# fpga2.net
KiCad netlist of a schematic drawn in Altium Designer
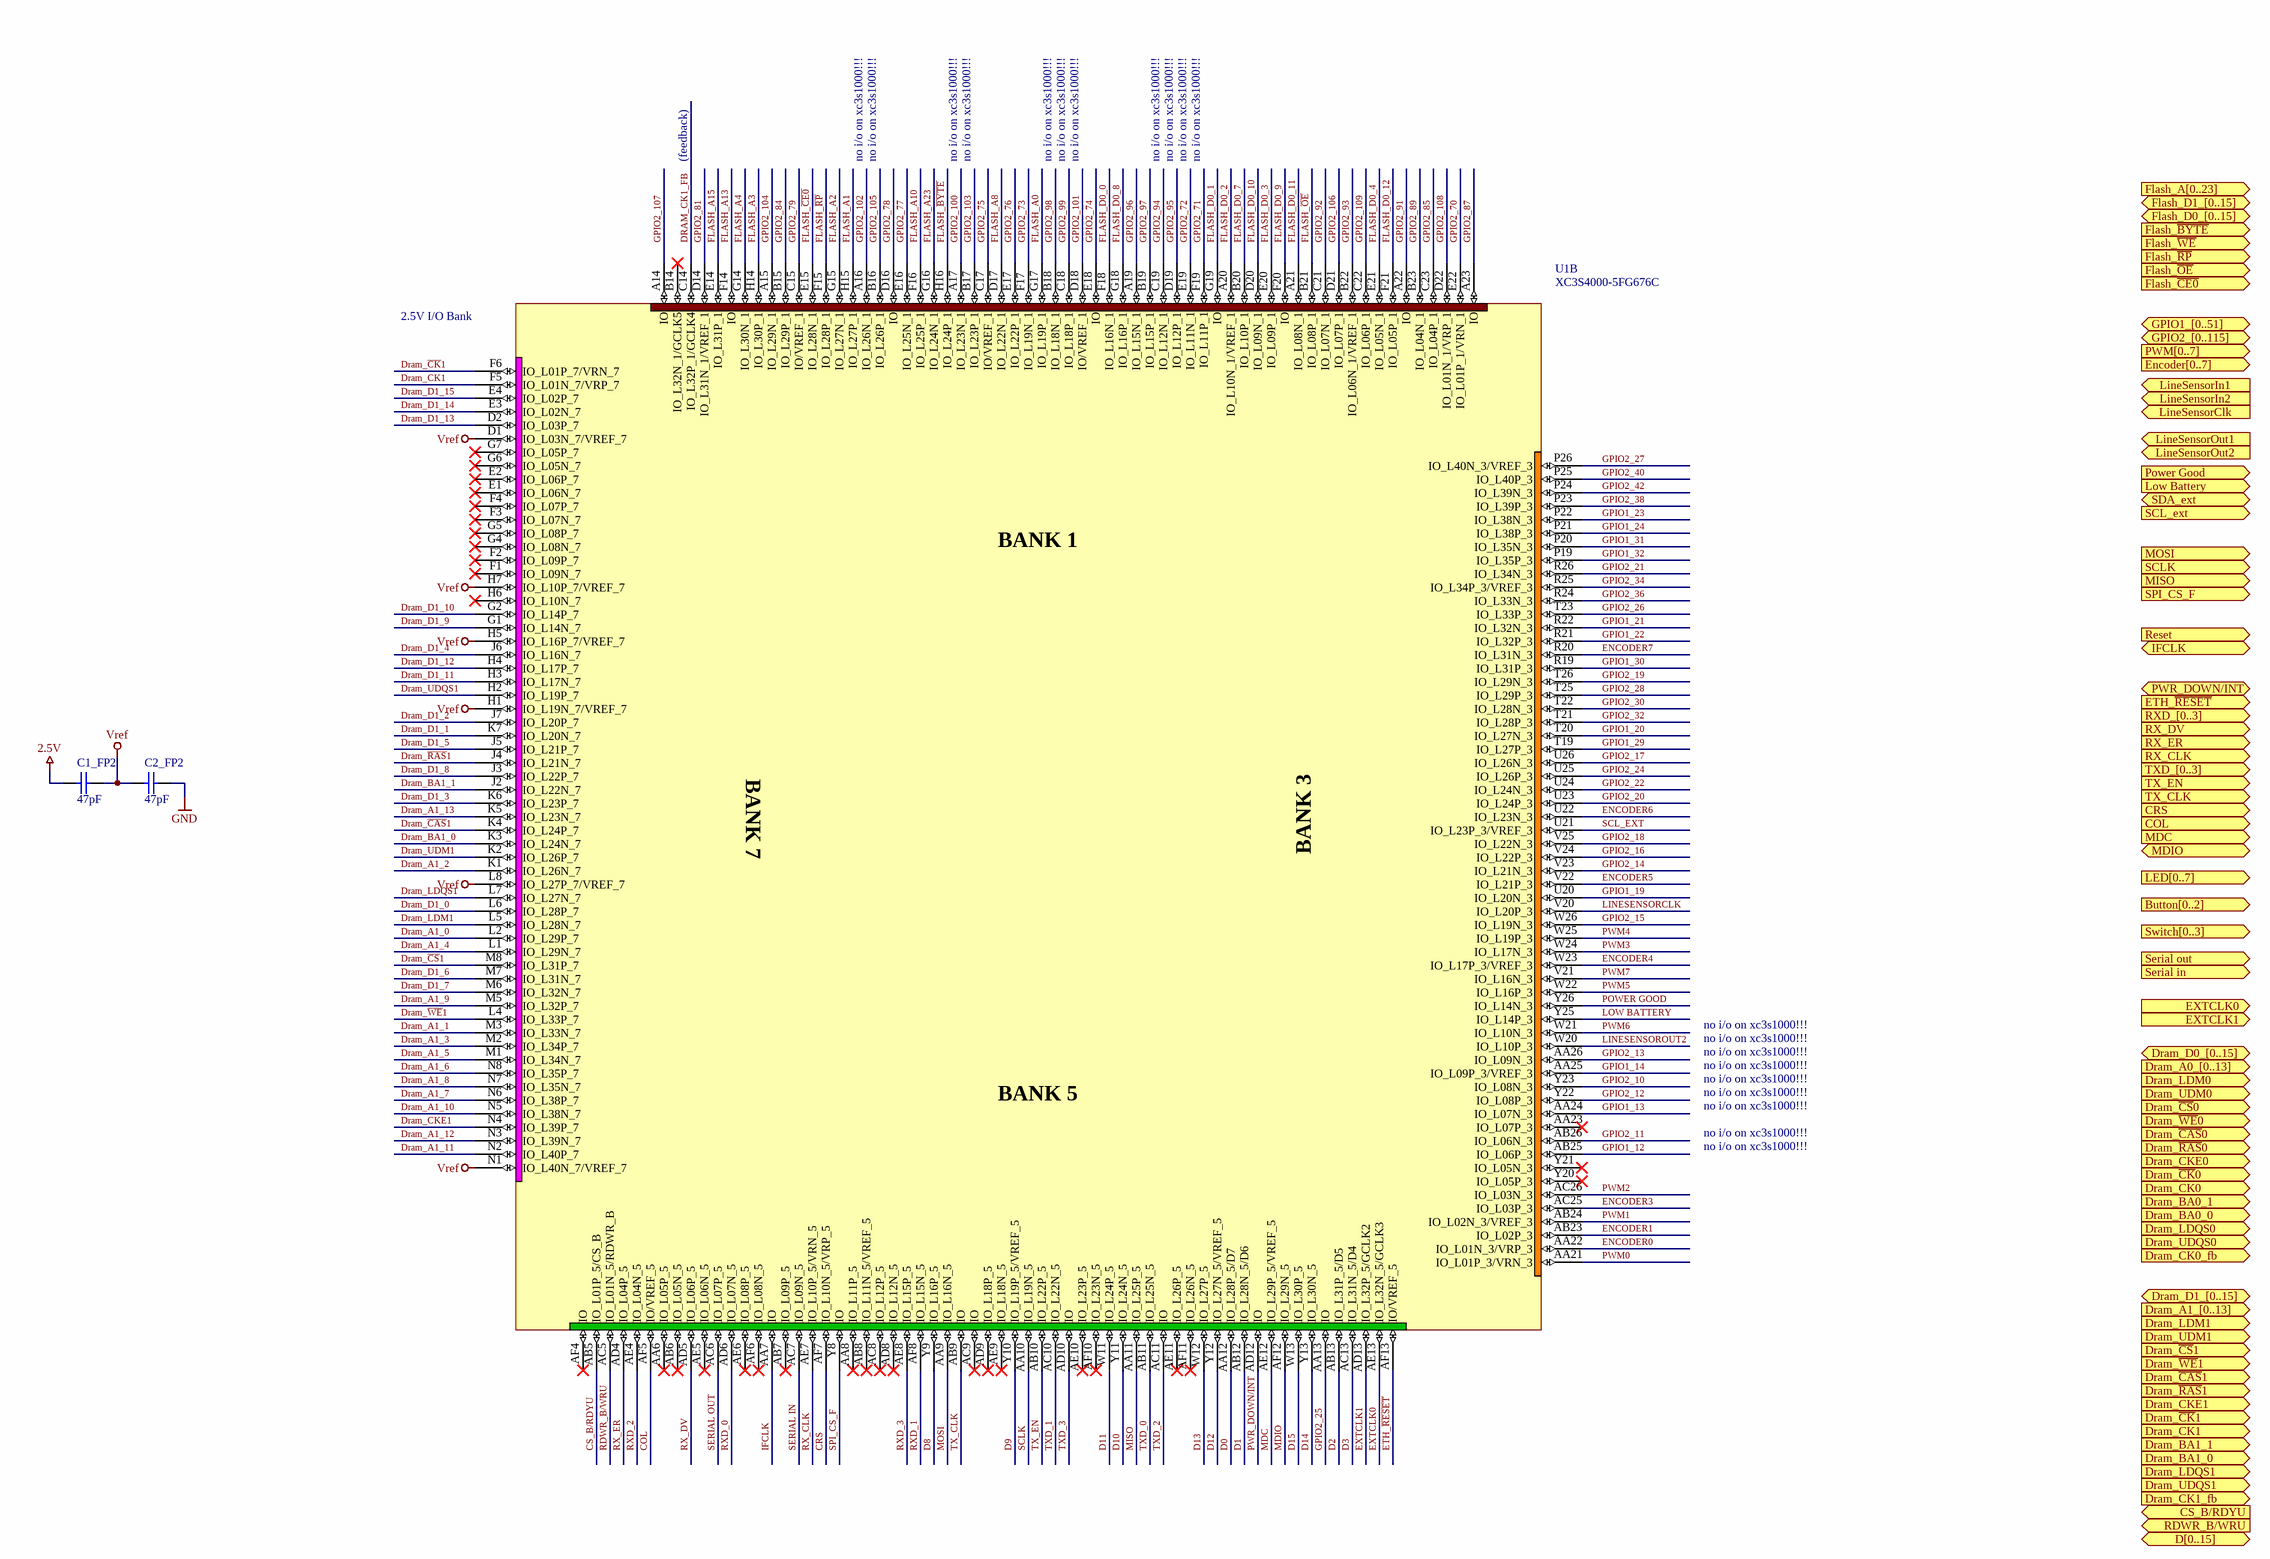
[diagram p0: fpga2.SCHDOC]

(export (version "E")
  (design (tool "Eeschema 10.0.6"))
  (components
    (comp (ref "C1_FP2")
      (value "47pF")
      (footprint "0402")
      (description "Capacitor")
      (fields
        (field (name "MANUFACTURER") "Murata")
        (field (name "PART NUMBER") "GRM1555C1H470JZ01D")
        (field (name "PUBLISHER") "Altium Limited")
      )
      (libsource (lib "Miscellaneous Devices") (part "Cap"))
    )
    (comp (ref "C2_FP2")
      (value "47pF")
      (footprint "0402")
      (description "Capacitor")
      (fields
        (field (name "MANUFACTURER") "Murata")
        (field (name "PART NUMBER") "GRM1555C1H470JZ01D")
        (field (name "PUBLISHER") "Altium Limited")
      )
      (libsource (lib "Miscellaneous Devices") (part "Cap"))
    )
    (comp (ref "U1")
      (value "XC3S4000-5FG676C")
      (footprint "FG676")
      (description "Spartan-3 1.2V FPGA, 487 User I/Os, 676-ball FBGA, High Performance, Commercial Grade")
      (fields (field (name "MANUFACTURER") "Xilinx") (field (name "PUBLISHER") "Altium Limited"))
      (libsource (lib "gecko3-user") (part "XC3S1500-5FG676C"))
    )
  )
  (nets
    (net (code "211") (name "/COL") (class "Default")
      (node (ref "U1") (pin "AF5") (pinfunction "IO/VREF_5_AF5") (pintype "bidirectional"))
    )
    (net (code "212") (name "/CRS") (class "Default")
      (node (ref "U1") (pin "AF7") (pinfunction "IO_L10N_5/VRP_5_AF7") (pintype "bidirectional"))
    )
    (net (code "213") (name "/CS_B{slash}RDYU") (class "Default")
      (node (ref "U1") (pin "AB5") (pinfunction "IO_L01P_5/CS_B_AB5") (pintype "bidirectional"))
    )
    (net (code "214") (name "/D0") (class "Default")
      (node (ref "U1") (pin "AA12") (pinfunction "IO_L28P_5/D7_AA12") (pintype "bidirectional"))
    )
    (net (code "215") (name "/D1") (class "Default")
      (node (ref "U1") (pin "AB12") (pinfunction "IO_L28N_5/D6_AB12") (pintype "bidirectional"))
    )
    (net (code "216") (name "/D2") (class "Default")
      (node (ref "U1") (pin "AB13") (pinfunction "IO_L31P_5/D5_AB13") (pintype "bidirectional"))
    )
    (net (code "217") (name "/D3") (class "Default")
      (node (ref "U1") (pin "AC13") (pinfunction "IO_L31N_5/D4_AC13") (pintype "bidirectional"))
    )
    (net (code "218") (name "/D8") (class "Default")
      (node (ref "U1") (pin "Y9") (pinfunction "IO_L16P_5_Y9") (pintype "bidirectional"))
    )
    (net (code "219") (name "/D9") (class "Default")
      (node (ref "U1") (pin "Y10") (pinfunction "IO_L19P_5/VREF_5_Y10") (pintype "bidirectional"))
    )
    (net (code "220") (name "/D10") (class "Default")
      (node (ref "U1") (pin "Y11") (pinfunction "IO_L24N_5_Y11") (pintype "bidirectional"))
    )
    (net (code "221") (name "/D11") (class "Default")
      (node (ref "U1") (pin "W11") (pinfunction "IO_L24P_5_W11") (pintype "bidirectional"))
    )
    (net (code "222") (name "/D12") (class "Default")
      (node (ref "U1") (pin "Y12") (pinfunction "IO_L27N_5/VREF_5_Y12") (pintype "bidirectional"))
    )
    (net (code "223") (name "/D13") (class "Default")
      (node (ref "U1") (pin "W12") (pinfunction "IO_L27P_5_W12") (pintype "bidirectional"))
    )
    (net (code "224") (name "/D14") (class "Default")
      (node (ref "U1") (pin "Y13") (pinfunction "IO_L30N_5_Y13") (pintype "bidirectional"))
    )
    (net (code "225") (name "/D15") (class "Default")
      (node (ref "U1") (pin "W13") (pinfunction "IO_L30P_5_W13") (pintype "bidirectional"))
    )
    (net (code "226") (name "/DRAM_CK1_FB") (class "Default")
      (node (ref "U1") (pin "C14") (pinfunction "IO_L32P_1/GCLK4_C14") (pintype "bidirectional"))
    )
    (net (code "229") (name "/Dram_A1_0") (class "Default")
      (node (ref "U1") (pin "L2") (pinfunction "IO_L29P_7_L2") (pintype "bidirectional"))
    )
    (net (code "230") (name "/Dram_A1_1") (class "Default")
      (node (ref "U1") (pin "M3") (pinfunction "IO_L33N_7_M3") (pintype "bidirectional"))
    )
    (net (code "231") (name "/Dram_A1_2") (class "Default")
      (node (ref "U1") (pin "K1") (pinfunction "IO_L26N_7_K1") (pintype "bidirectional"))
    )
    (net (code "232") (name "/Dram_A1_3") (class "Default")
      (node (ref "U1") (pin "M2") (pinfunction "IO_L34P_7_M2") (pintype "bidirectional"))
    )
    (net (code "233") (name "/Dram_A1_4") (class "Default")
      (node (ref "U1") (pin "L1") (pinfunction "IO_L29N_7_L1") (pintype "bidirectional"))
    )
    (net (code "234") (name "/Dram_A1_5") (class "Default")
      (node (ref "U1") (pin "M1") (pinfunction "IO_L34N_7_M1") (pintype "bidirectional"))
    )
    (net (code "235") (name "/Dram_A1_6") (class "Default")
      (node (ref "U1") (pin "N8") (pinfunction "IO_L35P_7_N8") (pintype "bidirectional"))
    )
    (net (code "236") (name "/Dram_A1_7") (class "Default")
      (node (ref "U1") (pin "N6") (pinfunction "IO_L38P_7_N6") (pintype "bidirectional"))
    )
    (net (code "237") (name "/Dram_A1_8") (class "Default")
      (node (ref "U1") (pin "N7") (pinfunction "IO_L35N_7_N7") (pintype "bidirectional"))
    )
    (net (code "238") (name "/Dram_A1_9") (class "Default")
      (node (ref "U1") (pin "M5") (pinfunction "IO_L32P_7_M5") (pintype "bidirectional"))
    )
    (net (code "239") (name "/Dram_A1_10") (class "Default")
      (node (ref "U1") (pin "N5") (pinfunction "IO_L38N_7_N5") (pintype "bidirectional"))
    )
    (net (code "240") (name "/Dram_A1_11") (class "Default")
      (node (ref "U1") (pin "N2") (pinfunction "IO_L40P_7_N2") (pintype "bidirectional"))
    )
    (net (code "241") (name "/Dram_A1_12") (class "Default")
      (node (ref "U1") (pin "N3") (pinfunction "IO_L39N_7_N3") (pintype "bidirectional"))
    )
    (net (code "242") (name "/Dram_A1_13") (class "Default")
      (node (ref "U1") (pin "K5") (pinfunction "IO_L23N_7_K5") (pintype "bidirectional"))
    )
    (net (code "246") (name "/Dram_BA1_0") (class "Default")
      (node (ref "U1") (pin "K3") (pinfunction "IO_L24N_7_K3") (pintype "bidirectional"))
    )
    (net (code "247") (name "/Dram_BA1_1") (class "Default")
      (node (ref "U1") (pin "J2") (pinfunction "IO_L22N_7_J2") (pintype "bidirectional"))
    )
    (net (code "250") (name "/Dram_CK1") (class "Default")
      (node (ref "U1") (pin "F5") (pinfunction "IO_L01N_7/VRP_7_F5") (pintype "bidirectional"))
    )
    (net (code "253") (name "/Dram_CKE1") (class "Default")
      (node (ref "U1") (pin "N4") (pinfunction "IO_L39P_7_N4") (pintype "bidirectional"))
    )
    (net (code "255") (name "/Dram_D1_0") (class "Default")
      (node (ref "U1") (pin "L6") (pinfunction "IO_L28P_7_L6") (pintype "bidirectional"))
    )
    (net (code "256") (name "/Dram_D1_1") (class "Default")
      (node (ref "U1") (pin "K7") (pinfunction "IO_L20N_7_K7") (pintype "bidirectional"))
    )
    (net (code "257") (name "/Dram_D1_2") (class "Default")
      (node (ref "U1") (pin "J7") (pinfunction "IO_L20P_7_J7") (pintype "bidirectional"))
    )
    (net (code "258") (name "/Dram_D1_3") (class "Default")
      (node (ref "U1") (pin "K6") (pinfunction "IO_L23P_7_K6") (pintype "bidirectional"))
    )
    (net (code "259") (name "/Dram_D1_4") (class "Default")
      (node (ref "U1") (pin "J6") (pinfunction "IO_L16N_7_J6") (pintype "bidirectional"))
    )
    (net (code "260") (name "/Dram_D1_5") (class "Default")
      (node (ref "U1") (pin "J5") (pinfunction "IO_L21P_7_J5") (pintype "bidirectional"))
    )
    (net (code "261") (name "/Dram_D1_6") (class "Default")
      (node (ref "U1") (pin "M7") (pinfunction "IO_L31N_7_M7") (pintype "bidirectional"))
    )
    (net (code "262") (name "/Dram_D1_7") (class "Default")
      (node (ref "U1") (pin "M6") (pinfunction "IO_L32N_7_M6") (pintype "bidirectional"))
    )
    (net (code "263") (name "/Dram_D1_8") (class "Default")
      (node (ref "U1") (pin "J3") (pinfunction "IO_L22P_7_J3") (pintype "bidirectional"))
    )
    (net (code "264") (name "/Dram_D1_9") (class "Default")
      (node (ref "U1") (pin "G1") (pinfunction "IO_L14N_7_G1") (pintype "bidirectional"))
    )
    (net (code "265") (name "/Dram_D1_10") (class "Default")
      (node (ref "U1") (pin "G2") (pinfunction "IO_L14P_7_G2") (pintype "bidirectional"))
    )
    (net (code "266") (name "/Dram_D1_11") (class "Default")
      (node (ref "U1") (pin "H3") (pinfunction "IO_L17N_7_H3") (pintype "bidirectional"))
    )
    (net (code "267") (name "/Dram_D1_12") (class "Default")
      (node (ref "U1") (pin "H4") (pinfunction "IO_L17P_7_H4") (pintype "bidirectional"))
    )
    (net (code "268") (name "/Dram_D1_13") (class "Default")
      (node (ref "U1") (pin "D2") (pinfunction "IO_L03P_7_D2") (pintype "bidirectional"))
    )
    (net (code "269") (name "/Dram_D1_14") (class "Default")
      (node (ref "U1") (pin "E3") (pinfunction "IO_L02N_7_E3") (pintype "bidirectional"))
    )
    (net (code "270") (name "/Dram_D1_15") (class "Default")
      (node (ref "U1") (pin "E4") (pinfunction "IO_L02P_7_E4") (pintype "bidirectional"))
    )
    (net (code "273") (name "/Dram_LDM1") (class "Default")
      (node (ref "U1") (pin "L5") (pinfunction "IO_L28N_7_L5") (pintype "bidirectional"))
    )
    (net (code "275") (name "/Dram_LDQS1") (class "Default")
      (node (ref "U1") (pin "L7") (pinfunction "IO_L27N_7_L7") (pintype "bidirectional"))
    )
    (net (code "277") (name "/Dram_UDM1") (class "Default")
      (node (ref "U1") (pin "K2") (pinfunction "IO_L26P_7_K2") (pintype "bidirectional"))
    )
    (net (code "279") (name "/Dram_UDQS1") (class "Default")
      (node (ref "U1") (pin "H2") (pinfunction "IO_L19P_7_H2") (pintype "bidirectional"))
    )
    (net (code "281") (name "/Dram_~{CAS}1") (class "Default")
      (node (ref "U1") (pin "K4") (pinfunction "IO_L24P_7_K4") (pintype "bidirectional"))
    )
    (net (code "283") (name "/Dram_~{CK}1") (class "Default")
      (node (ref "U1") (pin "F6") (pinfunction "IO_L01P_7/VRN_7_F6") (pintype "bidirectional"))
    )
    (net (code "285") (name "/Dram_~{CS}1") (class "Default")
      (node (ref "U1") (pin "M8") (pinfunction "IO_L31P_7_M8") (pintype "bidirectional"))
    )
    (net (code "287") (name "/Dram_~{RAS}1") (class "Default")
      (node (ref "U1") (pin "J4") (pinfunction "IO_L21N_7_J4") (pintype "bidirectional"))
    )
    (net (code "289") (name "/Dram_~{WE}1") (class "Default")
      (node (ref "U1") (pin "L4") (pinfunction "IO_L33P_7_L4") (pintype "bidirectional"))
    )
    (net (code "290") (name "/ENCODER0") (class "Default")
      (node (ref "U1") (pin "AA22") (pinfunction "IO_L01N_3/VRP_3_AA22") (pintype "bidirectional"))
    )
    (net (code "291") (name "/ENCODER1") (class "Default")
      (node (ref "U1") (pin "AB23") (pinfunction "IO_L02P_3_AB23") (pintype "bidirectional"))
    )
    (net (code "292") (name "/ENCODER3") (class "Default")
      (node (ref "U1") (pin "AC25") (pinfunction "IO_L03P_3_AC25") (pintype "bidirectional"))
    )
    (net (code "293") (name "/ENCODER4") (class "Default")
      (node (ref "U1") (pin "W23") (pinfunction "IO_L17P_3/VREF_3_W23") (pintype "bidirectional"))
    )
    (net (code "294") (name "/ENCODER5") (class "Default")
      (node (ref "U1") (pin "V22") (pinfunction "IO_L21P_3_V22") (pintype "bidirectional"))
    )
    (net (code "295") (name "/ENCODER6") (class "Default")
      (node (ref "U1") (pin "U22") (pinfunction "IO_L23N_3_U22") (pintype "bidirectional"))
    )
    (net (code "296") (name "/ENCODER7") (class "Default")
      (node (ref "U1") (pin "R20") (pinfunction "IO_L31N_3_R20") (pintype "bidirectional"))
    )
    (net (code "297") (name "/ETH_~{RESET}") (class "Default")
      (node (ref "U1") (pin "AF13") (pinfunction "IO/VREF_5_AF13") (pintype "bidirectional"))
    )
    (net (code "298") (name "/EXTCLK0") (class "Default")
      (node (ref "U1") (pin "AE13") (pinfunction "IO_L32N_5/GCLK3_AE13") (pintype "bidirectional"))
    )
    (net (code "299") (name "/EXTCLK1") (class "Default")
      (node (ref "U1") (pin "AD13") (pinfunction "IO_L32P_5/GCLK2_AD13") (pintype "bidirectional"))
    )
    (net (code "301") (name "/FLASH_A0") (class "Default")
      (node (ref "U1") (pin "G17") (pinfunction "IO_L19P_1_G17") (pintype "bidirectional"))
    )
    (net (code "302") (name "/FLASH_A1") (class "Default")
      (node (ref "U1") (pin "H15") (pinfunction "IO_L27P_1_H15") (pintype "bidirectional"))
    )
    (net (code "303") (name "/FLASH_A2") (class "Default")
      (node (ref "U1") (pin "G15") (pinfunction "IO_L27N_1_G15") (pintype "bidirectional"))
    )
    (net (code "304") (name "/FLASH_A3") (class "Default")
      (node (ref "U1") (pin "H14") (pinfunction "IO_L30P_1_H14") (pintype "bidirectional"))
    )
    (net (code "305") (name "/FLASH_A4") (class "Default")
      (node (ref "U1") (pin "G14") (pinfunction "IO_L30N_1_G14") (pintype "bidirectional"))
    )
    (net (code "306") (name "/FLASH_A8") (class "Default")
      (node (ref "U1") (pin "D17") (pinfunction "IO_L22N_1_D17") (pintype "bidirectional"))
    )
    (net (code "307") (name "/FLASH_A10") (class "Default")
      (node (ref "U1") (pin "F16") (pinfunction "IO_L25P_1_F16") (pintype "bidirectional"))
    )
    (net (code "308") (name "/FLASH_A13") (class "Default")
      (node (ref "U1") (pin "F14") (pinfunction "IO_F14") (pintype "bidirectional"))
    )
    (net (code "309") (name "/FLASH_A15") (class "Default")
      (node (ref "U1") (pin "E14") (pinfunction "IO_L31P_1_E14") (pintype "bidirectional"))
    )
    (net (code "310") (name "/FLASH_A23") (class "Default")
      (node (ref "U1") (pin "G16") (pinfunction "IO_L24N_1_G16") (pintype "bidirectional"))
    )
    (net (code "311") (name "/FLASH_D0_0") (class "Default")
      (node (ref "U1") (pin "F18") (pinfunction "IO_L16N_1_F18") (pintype "bidirectional"))
    )
    (net (code "312") (name "/FLASH_D0_1") (class "Default")
      (node (ref "U1") (pin "G19") (pinfunction "IO_G19") (pintype "bidirectional"))
    )
    (net (code "313") (name "/FLASH_D0_2") (class "Default")
      (node (ref "U1") (pin "A20") (pinfunction "IO_L10N_1/VREF_1_A20") (pintype "bidirectional"))
    )
    (net (code "314") (name "/FLASH_D0_3") (class "Default")
      (node (ref "U1") (pin "E20") (pinfunction "IO_L09P_1_E20") (pintype "bidirectional"))
    )
    (net (code "315") (name "/FLASH_D0_4") (class "Default")
      (node (ref "U1") (pin "E21") (pinfunction "IO_L05N_1_E21") (pintype "bidirectional"))
    )
    (net (code "316") (name "/FLASH_D0_7") (class "Default")
      (node (ref "U1") (pin "B20") (pinfunction "IO_L10P_1_B20") (pintype "bidirectional"))
    )
    (net (code "317") (name "/FLASH_D0_8") (class "Default")
      (node (ref "U1") (pin "G18") (pinfunction "IO_L16P_1_G18") (pintype "bidirectional"))
    )
    (net (code "318") (name "/FLASH_D0_9") (class "Default")
      (node (ref "U1") (pin "F20") (pinfunction "IO_F20") (pintype "bidirectional"))
    )
    (net (code "319") (name "/FLASH_D0_10") (class "Default")
      (node (ref "U1") (pin "D20") (pinfunction "IO_L09N_1_D20") (pintype "bidirectional"))
    )
    (net (code "320") (name "/FLASH_D0_11") (class "Default")
      (node (ref "U1") (pin "A21") (pinfunction "IO_L08N_1_A21") (pintype "bidirectional"))
    )
    (net (code "321") (name "/FLASH_D0_12") (class "Default")
      (node (ref "U1") (pin "F21") (pinfunction "IO_L05P_1_F21") (pintype "bidirectional"))
    )
    (net (code "322") (name "/FLASH_~{BYTE}") (class "Default")
      (node (ref "U1") (pin "H16") (pinfunction "IO_L24P_1_H16") (pintype "bidirectional"))
    )
    (net (code "323") (name "/FLASH_~{CE0}") (class "Default")
      (node (ref "U1") (pin "E15") (pinfunction "IO_L28N_1_E15") (pintype "bidirectional"))
    )
    (net (code "324") (name "/FLASH_~{OE}") (class "Default")
      (node (ref "U1") (pin "B21") (pinfunction "IO_L08P_1_B21") (pintype "bidirectional"))
    )
    (net (code "325") (name "/FLASH_~{RP}") (class "Default")
      (node (ref "U1") (pin "F15") (pinfunction "IO_L28P_1_F15") (pintype "bidirectional"))
    )
    (net (code "334") (name "/GPIO1_12") (class "Default")
      (node (ref "U1") (pin "AB25") (pinfunction "IO_L06P_3_AB25") (pintype "bidirectional"))
    )
    (net (code "335") (name "/GPIO1_13") (class "Default")
      (node (ref "U1") (pin "AA24") (pinfunction "IO_L07N_3_AA24") (pintype "bidirectional"))
    )
    (net (code "336") (name "/GPIO1_14") (class "Default")
      (node (ref "U1") (pin "AA25") (pinfunction "IO_L09P_3/VREF_3_AA25") (pintype "bidirectional"))
    )
    (net (code "337") (name "/GPIO1_19") (class "Default")
      (node (ref "U1") (pin "U20") (pinfunction "IO_L20N_3_U20") (pintype "bidirectional"))
    )
    (net (code "338") (name "/GPIO1_20") (class "Default")
      (node (ref "U1") (pin "T20") (pinfunction "IO_L27N_3_T20") (pintype "bidirectional"))
    )
    (net (code "339") (name "/GPIO1_21") (class "Default")
      (node (ref "U1") (pin "R22") (pinfunction "IO_L32N_3_R22") (pintype "bidirectional"))
    )
    (net (code "340") (name "/GPIO1_22") (class "Default")
      (node (ref "U1") (pin "R21") (pinfunction "IO_L32P_3_R21") (pintype "bidirectional"))
    )
    (net (code "341") (name "/GPIO1_23") (class "Default")
      (node (ref "U1") (pin "P22") (pinfunction "IO_L38N_3_P22") (pintype "bidirectional"))
    )
    (net (code "342") (name "/GPIO1_24") (class "Default")
      (node (ref "U1") (pin "P21") (pinfunction "IO_L38P_3_P21") (pintype "bidirectional"))
    )
    (net (code "343") (name "/GPIO1_29") (class "Default")
      (node (ref "U1") (pin "T19") (pinfunction "IO_L27P_3_T19") (pintype "bidirectional"))
    )
    (net (code "344") (name "/GPIO1_30") (class "Default")
      (node (ref "U1") (pin "R19") (pinfunction "IO_L31P_3_R19") (pintype "bidirectional"))
    )
    (net (code "345") (name "/GPIO1_31") (class "Default")
      (node (ref "U1") (pin "P20") (pinfunction "IO_L35N_3_P20") (pintype "bidirectional"))
    )
    (net (code "346") (name "/GPIO1_32") (class "Default")
      (node (ref "U1") (pin "P19") (pinfunction "IO_L35P_3_P19") (pintype "bidirectional"))
    )
    (net (code "348") (name "/GPIO2_10") (class "Default")
      (node (ref "U1") (pin "Y23") (pinfunction "IO_L08N_3_Y23") (pintype "bidirectional"))
    )
    (net (code "349") (name "/GPIO2_11") (class "Default")
      (node (ref "U1") (pin "AB26") (pinfunction "IO_L06N_3_AB26") (pintype "bidirectional"))
    )
    (net (code "350") (name "/GPIO2_12") (class "Default")
      (node (ref "U1") (pin "Y22") (pinfunction "IO_L08P_3_Y22") (pintype "bidirectional"))
    )
    (net (code "351") (name "/GPIO2_13") (class "Default")
      (node (ref "U1") (pin "AA26") (pinfunction "IO_L09N_3_AA26") (pintype "bidirectional"))
    )
    (net (code "352") (name "/GPIO2_14") (class "Default")
      (node (ref "U1") (pin "V23") (pinfunction "IO_L21N_3_V23") (pintype "bidirectional"))
    )
    (net (code "353") (name "/GPIO2_15") (class "Default")
      (node (ref "U1") (pin "W26") (pinfunction "IO_L19N_3_W26") (pintype "bidirectional"))
    )
    (net (code "354") (name "/GPIO2_16") (class "Default")
      (node (ref "U1") (pin "V24") (pinfunction "IO_L22P_3_V24") (pintype "bidirectional"))
    )
    (net (code "355") (name "/GPIO2_17") (class "Default")
      (node (ref "U1") (pin "U26") (pinfunction "IO_L26N_3_U26") (pintype "bidirectional"))
    )
    (net (code "356") (name "/GPIO2_18") (class "Default")
      (node (ref "U1") (pin "V25") (pinfunction "IO_L22N_3_V25") (pintype "bidirectional"))
    )
    (net (code "357") (name "/GPIO2_19") (class "Default")
      (node (ref "U1") (pin "T26") (pinfunction "IO_L29N_3_T26") (pintype "bidirectional"))
    )
    (net (code "358") (name "/GPIO2_20") (class "Default")
      (node (ref "U1") (pin "U23") (pinfunction "IO_L24P_3_U23") (pintype "bidirectional"))
    )
    (net (code "359") (name "/GPIO2_21") (class "Default")
      (node (ref "U1") (pin "R26") (pinfunction "IO_L34N_3_R26") (pintype "bidirectional"))
    )
    (net (code "360") (name "/GPIO2_22") (class "Default")
      (node (ref "U1") (pin "U24") (pinfunction "IO_L24N_3_U24") (pintype "bidirectional"))
    )
    (net (code "361") (name "/GPIO2_24") (class "Default")
      (node (ref "U1") (pin "U25") (pinfunction "IO_L26P_3_U25") (pintype "bidirectional"))
    )
    (net (code "362") (name "/GPIO2_25") (class "Default")
      (node (ref "U1") (pin "AA13") (pinfunction "IO_AA13") (pintype "bidirectional"))
    )
    (net (code "363") (name "/GPIO2_26") (class "Default")
      (node (ref "U1") (pin "T23") (pinfunction "IO_L33P_3_T23") (pintype "bidirectional"))
    )
    (net (code "364") (name "/GPIO2_27") (class "Default")
      (node (ref "U1") (pin "P26") (pinfunction "IO_L40N_3/VREF_3_P26") (pintype "bidirectional"))
    )
    (net (code "365") (name "/GPIO2_28") (class "Default")
      (node (ref "U1") (pin "T25") (pinfunction "IO_L29P_3_T25") (pintype "bidirectional"))
    )
    (net (code "366") (name "/GPIO2_30") (class "Default")
      (node (ref "U1") (pin "T22") (pinfunction "IO_L28N_3_T22") (pintype "bidirectional"))
    )
    (net (code "367") (name "/GPIO2_32") (class "Default")
      (node (ref "U1") (pin "T21") (pinfunction "IO_L28P_3_T21") (pintype "bidirectional"))
    )
    (net (code "368") (name "/GPIO2_34") (class "Default")
      (node (ref "U1") (pin "R25") (pinfunction "IO_L34P_3/VREF_3_R25") (pintype "bidirectional"))
    )
    (net (code "369") (name "/GPIO2_36") (class "Default")
      (node (ref "U1") (pin "R24") (pinfunction "IO_L33N_3_R24") (pintype "bidirectional"))
    )
    (net (code "370") (name "/GPIO2_38") (class "Default")
      (node (ref "U1") (pin "P23") (pinfunction "IO_L39P_3_P23") (pintype "bidirectional"))
    )
    (net (code "371") (name "/GPIO2_40") (class "Default")
      (node (ref "U1") (pin "P25") (pinfunction "IO_L40P_3_P25") (pintype "bidirectional"))
    )
    (net (code "372") (name "/GPIO2_42") (class "Default")
      (node (ref "U1") (pin "P24") (pinfunction "IO_L39N_3_P24") (pintype "bidirectional"))
    )
    (net (code "373") (name "/GPIO2_70") (class "Default")
      (node (ref "U1") (pin "E22") (pinfunction "IO_L01P_1/VRN_1_E22") (pintype "bidirectional"))
    )
    (net (code "374") (name "/GPIO2_71") (class "Default")
      (node (ref "U1") (pin "F19") (pinfunction "IO_L11P_1_F19") (pintype "bidirectional"))
    )
    (net (code "375") (name "/GPIO2_72") (class "Default")
      (node (ref "U1") (pin "E19") (pinfunction "IO_L11N_1_E19") (pintype "bidirectional"))
    )
    (net (code "376") (name "/GPIO2_73") (class "Default")
      (node (ref "U1") (pin "F17") (pinfunction "IO_L19N_1_F17") (pintype "bidirectional"))
    )
    (net (code "377") (name "/GPIO2_74") (class "Default")
      (node (ref "U1") (pin "E18") (pinfunction "IO_E18") (pintype "bidirectional"))
    )
    (net (code "378") (name "/GPIO2_75") (class "Default")
      (node (ref "U1") (pin "C17") (pinfunction "IO/VREF_1_C17") (pintype "bidirectional"))
    )
    (net (code "379") (name "/GPIO2_76") (class "Default")
      (node (ref "U1") (pin "E17") (pinfunction "IO_L22P_1_E17") (pintype "bidirectional"))
    )
    (net (code "380") (name "/GPIO2_77") (class "Default")
      (node (ref "U1") (pin "E16") (pinfunction "IO_L25N_1_E16") (pintype "bidirectional"))
    )
    (net (code "381") (name "/GPIO2_78") (class "Default")
      (node (ref "U1") (pin "D16") (pinfunction "IO_D16") (pintype "bidirectional"))
    )
    (net (code "382") (name "/GPIO2_79") (class "Default")
      (node (ref "U1") (pin "C15") (pinfunction "IO/VREF_1_C15") (pintype "bidirectional"))
    )
    (net (code "383") (name "/GPIO2_81") (class "Default")
      (node (ref "U1") (pin "D14") (pinfunction "IO_L31N_1/VREF_1_D14") (pintype "bidirectional"))
    )
    (net (code "384") (name "/GPIO2_84") (class "Default")
      (node (ref "U1") (pin "B15") (pinfunction "IO_L29P_1_B15") (pintype "bidirectional"))
    )
    (net (code "385") (name "/GPIO2_85") (class "Default")
      (node (ref "U1") (pin "C23") (pinfunction "IO_L04P_1_C23") (pintype "bidirectional"))
    )
    (net (code "386") (name "/GPIO2_87") (class "Default")
      (node (ref "U1") (pin "A23") (pinfunction "IO_A23") (pintype "bidirectional"))
    )
    (net (code "387") (name "/GPIO2_89") (class "Default")
      (node (ref "U1") (pin "B23") (pinfunction "IO_L04N_1_B23") (pintype "bidirectional"))
    )
    (net (code "388") (name "/GPIO2_91") (class "Default")
      (node (ref "U1") (pin "A22") (pinfunction "IO_A22") (pintype "bidirectional"))
    )
    (net (code "389") (name "/GPIO2_92") (class "Default")
      (node (ref "U1") (pin "C21") (pinfunction "IO_L07N_1_C21") (pintype "bidirectional"))
    )
    (net (code "390") (name "/GPIO2_93") (class "Default")
      (node (ref "U1") (pin "B22") (pinfunction "IO_L06N_1/VREF_1_B22") (pintype "bidirectional"))
    )
    (net (code "391") (name "/GPIO2_94") (class "Default")
      (node (ref "U1") (pin "C19") (pinfunction "IO_L12N_1_C19") (pintype "bidirectional"))
    )
    (net (code "392") (name "/GPIO2_95") (class "Default")
      (node (ref "U1") (pin "D19") (pinfunction "IO_L12P_1_D19") (pintype "bidirectional"))
    )
    (net (code "393") (name "/GPIO2_96") (class "Default")
      (node (ref "U1") (pin "A19") (pinfunction "IO_L15N_1_A19") (pintype "bidirectional"))
    )
    (net (code "394") (name "/GPIO2_97") (class "Default")
      (node (ref "U1") (pin "B19") (pinfunction "IO_L15P_1_B19") (pintype "bidirectional"))
    )
    (net (code "395") (name "/GPIO2_98") (class "Default")
      (node (ref "U1") (pin "B18") (pinfunction "IO_L18N_1_B18") (pintype "bidirectional"))
    )
    (net (code "396") (name "/GPIO2_99") (class "Default")
      (node (ref "U1") (pin "C18") (pinfunction "IO_L18P_1_C18") (pintype "bidirectional"))
    )
    (net (code "397") (name "/GPIO2_100") (class "Default")
      (node (ref "U1") (pin "A17") (pinfunction "IO_L23N_1_A17") (pintype "bidirectional"))
    )
    (net (code "398") (name "/GPIO2_101") (class "Default")
      (node (ref "U1") (pin "D18") (pinfunction "IO/VREF_1_D18") (pintype "bidirectional"))
    )
    (net (code "399") (name "/GPIO2_102") (class "Default")
      (node (ref "U1") (pin "A16") (pinfunction "IO_L26N_1_A16") (pintype "bidirectional"))
    )
    (net (code "400") (name "/GPIO2_103") (class "Default")
      (node (ref "U1") (pin "B17") (pinfunction "IO_L23P_1_B17") (pintype "bidirectional"))
    )
    (net (code "401") (name "/GPIO2_104") (class "Default")
      (node (ref "U1") (pin "A15") (pinfunction "IO_L29N_1_A15") (pintype "bidirectional"))
    )
    (net (code "402") (name "/GPIO2_105") (class "Default")
      (node (ref "U1") (pin "B16") (pinfunction "IO_L26P_1_B16") (pintype "bidirectional"))
    )
    (net (code "403") (name "/GPIO2_106") (class "Default")
      (node (ref "U1") (pin "D21") (pinfunction "IO_L07P_1_D21") (pintype "bidirectional"))
    )
    (net (code "404") (name "/GPIO2_107") (class "Default")
      (node (ref "U1") (pin "A14") (pinfunction "IO_A14") (pintype "bidirectional"))
    )
    (net (code "405") (name "/GPIO2_108") (class "Default")
      (node (ref "U1") (pin "D22") (pinfunction "IO_L01N_1/VRP_1_D22") (pintype "bidirectional"))
    )
    (net (code "406") (name "/GPIO2_109") (class "Default")
      (node (ref "U1") (pin "C22") (pinfunction "IO_L06P_1_C22") (pintype "bidirectional"))
    )
    (net (code "408") (name "/IFCLK") (class "Default")
      (node (ref "U1") (pin "AA7") (pinfunction "IO_AA7") (pintype "bidirectional"))
    )
    (net (code "410") (name "/LINESENSORCLK") (class "Default")
      (node (ref "U1") (pin "V20") (pinfunction "IO_L20P_3_V20") (pintype "bidirectional"))
    )
    (net (code "411") (name "/LINESENSOROUT2") (class "Default")
      (node (ref "U1") (pin "W20") (pinfunction "IO_L10P_3_W20") (pintype "bidirectional"))
    )
    (net (code "412") (name "/LOW BATTERY") (class "Default")
      (node (ref "U1") (pin "Y25") (pinfunction "IO_L14P_3_Y25") (pintype "bidirectional"))
    )
    (net (code "419") (name "/MDC") (class "Default")
      (node (ref "U1") (pin "AE12") (pinfunction "IO_L29P_5/VREF_5_AE12") (pintype "bidirectional"))
    )
    (net (code "420") (name "/MDIO") (class "Default")
      (node (ref "U1") (pin "AF12") (pinfunction "IO_L29N_5_AF12") (pintype "bidirectional"))
    )
    (net (code "421") (name "/MISO") (class "Default")
      (node (ref "U1") (pin "AA11") (pinfunction "IO_L25P_5_AA11") (pintype "bidirectional"))
    )
    (net (code "422") (name "/MOSI") (class "Default")
      (node (ref "U1") (pin "AA9") (pinfunction "IO_L16N_5_AA9") (pintype "bidirectional"))
    )
    (net (code "423") (name "/POWER GOOD") (class "Default")
      (node (ref "U1") (pin "Y26") (pinfunction "IO_L14N_3_Y26") (pintype "bidirectional"))
    )
    (net (code "424") (name "/PWM0") (class "Default")
      (node (ref "U1") (pin "AA21") (pinfunction "IO_L01P_3/VRN_3_AA21") (pintype "bidirectional"))
    )
    (net (code "425") (name "/PWM1") (class "Default")
      (node (ref "U1") (pin "AB24") (pinfunction "IO_L02N_3/VREF_3_AB24") (pintype "bidirectional"))
    )
    (net (code "426") (name "/PWM2") (class "Default")
      (node (ref "U1") (pin "AC26") (pinfunction "IO_L03N_3_AC26") (pintype "bidirectional"))
    )
    (net (code "427") (name "/PWM3") (class "Default")
      (node (ref "U1") (pin "W24") (pinfunction "IO_L17N_3_W24") (pintype "bidirectional"))
    )
    (net (code "428") (name "/PWM4") (class "Default")
      (node (ref "U1") (pin "W25") (pinfunction "IO_L19P_3_W25") (pintype "bidirectional"))
    )
    (net (code "429") (name "/PWM5") (class "Default")
      (node (ref "U1") (pin "W22") (pinfunction "IO_L16P_3_W22") (pintype "bidirectional"))
    )
    (net (code "430") (name "/PWM6") (class "Default")
      (node (ref "U1") (pin "W21") (pinfunction "IO_L10N_3_W21") (pintype "bidirectional"))
    )
    (net (code "431") (name "/PWM7") (class "Default")
      (node (ref "U1") (pin "V21") (pinfunction "IO_L16N_3_V21") (pintype "bidirectional"))
    )
    (net (code "433") (name "/PWR_DOWN{slash}INT") (class "Default")
      (node (ref "U1") (pin "AD12") (pinfunction "IO_AD12") (pintype "bidirectional"))
    )
    (net (code "435") (name "/RDWR_B{slash}WRU") (class "Default")
      (node (ref "U1") (pin "AC5") (pinfunction "IO_L01N_5/RDWR_B_AC5") (pintype "bidirectional"))
    )
    (net (code "436") (name "/RXD_0") (class "Default")
      (node (ref "U1") (pin "AD6") (pinfunction "IO_L07N_5_AD6") (pintype "bidirectional"))
    )
    (net (code "437") (name "/RXD_1") (class "Default")
      (node (ref "U1") (pin "AF8") (pinfunction "IO_L15N_5_AF8") (pintype "bidirectional"))
    )
    (net (code "438") (name "/RXD_2") (class "Default")
      (node (ref "U1") (pin "AE4") (pinfunction "IO_L04N_5_AE4") (pintype "bidirectional"))
    )
    (net (code "439") (name "/RXD_3") (class "Default")
      (node (ref "U1") (pin "AE8") (pinfunction "IO_L15P_5_AE8") (pintype "bidirectional"))
    )
    (net (code "441") (name "/RX_CLK") (class "Default")
      (node (ref "U1") (pin "AE7") (pinfunction "IO_L10P_5/VRN_5_AE7") (pintype "bidirectional"))
    )
    (net (code "442") (name "/RX_DV") (class "Default")
      (node (ref "U1") (pin "AD5") (pinfunction "IO_L06P_5_AD5") (pintype "bidirectional"))
    )
    (net (code "443") (name "/RX_ER") (class "Default")
      (node (ref "U1") (pin "AD4") (pinfunction "IO_L04P_5_AD4") (pintype "bidirectional"))
    )
    (net (code "445") (name "/SCLK") (class "Default")
      (node (ref "U1") (pin "AA10") (pinfunction "IO_L19N_5_AA10") (pintype "bidirectional"))
    )
    (net (code "446") (name "/SCL_EXT") (class "Default")
      (node (ref "U1") (pin "U21") (pinfunction "IO_L23P_3/VREF_3_U21") (pintype "bidirectional"))
    )
    (net (code "449") (name "/SERIAL IN") (class "Default")
      (node (ref "U1") (pin "AC7") (pinfunction "IO_L09N_5_AC7") (pintype "bidirectional"))
    )
    (net (code "450") (name "/SERIAL OUT") (class "Default")
      (node (ref "U1") (pin "AC6") (pinfunction "IO_L07P_5_AC6") (pintype "bidirectional"))
    )
    (net (code "451") (name "/SPI_CS_F") (class "Default")
      (node (ref "U1") (pin "Y8") (pinfunction "IO_Y8") (pintype "bidirectional"))
    )
    (net (code "455") (name "/TXD_0") (class "Default")
      (node (ref "U1") (pin "AB11") (pinfunction "IO_L25N_5_AB11") (pintype "bidirectional"))
    )
    (net (code "456") (name "/TXD_1") (class "Default")
      (node (ref "U1") (pin "AC10") (pinfunction "IO_L22N_5_AC10") (pintype "bidirectional"))
    )
    (net (code "457") (name "/TXD_2") (class "Default")
      (node (ref "U1") (pin "AC11") (pinfunction "IO_AC11") (pintype "bidirectional"))
    )
    (net (code "458") (name "/TXD_3") (class "Default")
      (node (ref "U1") (pin "AD10") (pinfunction "IO_AD10") (pintype "bidirectional"))
    )
    (net (code "460") (name "/TX_CLK") (class "Default")
      (node (ref "U1") (pin "AB9") (pinfunction "IO_AB9") (pintype "bidirectional"))
    )
    (net (code "461") (name "/TX_EN") (class "Default")
      (node (ref "U1") (pin "AB10") (pinfunction "IO_L22P_5_AB10") (pintype "bidirectional"))
    )
    (net (code "462") (name "2.5V") (class "Default")
      (node (ref "C1_FP2") (pin "2") (pinfunction "2_2") (pintype "passive"))
    )
    (net (code "463") (name "GND") (class "Default")
      (node (ref "C2_FP2") (pin "1") (pinfunction "1_1") (pintype "passive"))
    )
    (net (code "464") (name "Vref") (class "Default")
      (node (ref "C1_FP2") (pin "1") (pinfunction "1_1") (pintype "passive"))
      (node (ref "C2_FP2") (pin "2") (pinfunction "2_2") (pintype "passive"))
      (node (ref "U1") (pin "D1") (pinfunction "IO_L03N_7/VREF_7_D1") (pintype "bidirectional"))
      (node (ref "U1") (pin "H1") (pinfunction "IO_L19N_7/VREF_7_H1") (pintype "bidirectional"))
      (node (ref "U1") (pin "H5") (pinfunction "IO_L16P_7/VREF_7_H5") (pintype "bidirectional"))
      (node (ref "U1") (pin "H7") (pinfunction "IO_L10P_7/VREF_7_H7") (pintype "bidirectional"))
      (node (ref "U1") (pin "L8") (pinfunction "IO_L27P_7/VREF_7_L8") (pintype "bidirectional"))
      (node (ref "U1") (pin "N1") (pinfunction "IO_L40N_7/VREF_7_N1") (pintype "bidirectional"))
    )
    (net (code "465") (name "unconnected-(U1B-IO-PadAC9)") (class "Default")
      (node (ref "U1") (pin "AC9") (pinfunction "IO_AC9") (pintype "bidirectional+no_connect"))
    )
    (net (code "466") (name "unconnected-(U1B-IO-PadAF4)") (class "Default")
      (node (ref "U1") (pin "AF4") (pinfunction "IO_AF4") (pintype "bidirectional+no_connect"))
    )
    (net (code "467") (name "unconnected-(U1B-IO_L05N_3-PadY21)") (class "Default")
      (node (ref "U1") (pin "Y21") (pinfunction "IO_L05N_3_Y21") (pintype "bidirectional+no_connect"))
    )
    (net (code "468") (name "unconnected-(U1B-IO_L05N_5-PadAB6)") (class "Default")
      (node (ref "U1") (pin "AB6") (pinfunction "IO_L05N_5_AB6") (pintype "bidirectional+no_connect"))
    )
    (net (code "469") (name "unconnected-(U1B-IO_L05N_7-PadG6)") (class "Default")
      (node (ref "U1") (pin "G6") (pinfunction "IO_L05N_7_G6") (pintype "bidirectional+no_connect"))
    )
    (net (code "470") (name "unconnected-(U1B-IO_L05P_3-PadY20)") (class "Default")
      (node (ref "U1") (pin "Y20") (pinfunction "IO_L05P_3_Y20") (pintype "bidirectional+no_connect"))
    )
    (net (code "471") (name "unconnected-(U1B-IO_L05P_5-PadAA6)") (class "Default")
      (node (ref "U1") (pin "AA6") (pinfunction "IO_L05P_5_AA6") (pintype "bidirectional+no_connect"))
    )
    (net (code "472") (name "unconnected-(U1B-IO_L05P_7-PadG7)") (class "Default")
      (node (ref "U1") (pin "G7") (pinfunction "IO_L05P_7_G7") (pintype "bidirectional+no_connect"))
    )
    (net (code "473") (name "unconnected-(U1B-IO_L06N_5-PadAE5)") (class "Default")
      (node (ref "U1") (pin "AE5") (pinfunction "IO_L06N_5_AE5") (pintype "bidirectional+no_connect"))
    )
    (net (code "474") (name "unconnected-(U1B-IO_L06N_7-PadE1)") (class "Default")
      (node (ref "U1") (pin "E1") (pinfunction "IO_L06N_7_E1") (pintype "bidirectional+no_connect"))
    )
    (net (code "475") (name "unconnected-(U1B-IO_L06P_7-PadE2)") (class "Default")
      (node (ref "U1") (pin "E2") (pinfunction "IO_L06P_7_E2") (pintype "bidirectional+no_connect"))
    )
    (net (code "476") (name "unconnected-(U1B-IO_L07N_7-PadF3)") (class "Default")
      (node (ref "U1") (pin "F3") (pinfunction "IO_L07N_7_F3") (pintype "bidirectional+no_connect"))
    )
    (net (code "477") (name "unconnected-(U1B-IO_L07P_3-PadAA23)") (class "Default")
      (node (ref "U1") (pin "AA23") (pinfunction "IO_L07P_3_AA23") (pintype "bidirectional+no_connect"))
    )
    (net (code "478") (name "unconnected-(U1B-IO_L07P_7-PadF4)") (class "Default")
      (node (ref "U1") (pin "F4") (pinfunction "IO_L07P_7_F4") (pintype "bidirectional+no_connect"))
    )
    (net (code "479") (name "unconnected-(U1B-IO_L08N_5-PadAF6)") (class "Default")
      (node (ref "U1") (pin "AF6") (pinfunction "IO_L08N_5_AF6") (pintype "bidirectional+no_connect"))
    )
    (net (code "480") (name "unconnected-(U1B-IO_L08N_7-PadG4)") (class "Default")
      (node (ref "U1") (pin "G4") (pinfunction "IO_L08N_7_G4") (pintype "bidirectional+no_connect"))
    )
    (net (code "481") (name "unconnected-(U1B-IO_L08P_5-PadAE6)") (class "Default")
      (node (ref "U1") (pin "AE6") (pinfunction "IO_L08P_5_AE6") (pintype "bidirectional+no_connect"))
    )
    (net (code "482") (name "unconnected-(U1B-IO_L08P_7-PadG5)") (class "Default")
      (node (ref "U1") (pin "G5") (pinfunction "IO_L08P_7_G5") (pintype "bidirectional+no_connect"))
    )
    (net (code "483") (name "unconnected-(U1B-IO_L09N_7-PadF1)") (class "Default")
      (node (ref "U1") (pin "F1") (pinfunction "IO_L09N_7_F1") (pintype "bidirectional+no_connect"))
    )
    (net (code "484") (name "unconnected-(U1B-IO_L09P_5-PadAB7)") (class "Default")
      (node (ref "U1") (pin "AB7") (pinfunction "IO_L09P_5_AB7") (pintype "bidirectional+no_connect"))
    )
    (net (code "485") (name "unconnected-(U1B-IO_L09P_7-PadF2)") (class "Default")
      (node (ref "U1") (pin "F2") (pinfunction "IO_L09P_7_F2") (pintype "bidirectional+no_connect"))
    )
    (net (code "486") (name "unconnected-(U1B-IO_L10N_7-PadH6)") (class "Default")
      (node (ref "U1") (pin "H6") (pinfunction "IO_L10N_7_H6") (pintype "bidirectional+no_connect"))
    )
    (net (code "487") (name "unconnected-(U1B-IO_L11N_5{slash}VREF_5-PadAB8)") (class "Default")
      (node (ref "U1") (pin "AB8") (pinfunction "IO_L11N_5/VREF_5_AB8") (pintype "bidirectional+no_connect"))
    )
    (net (code "488") (name "unconnected-(U1B-IO_L11P_5-PadAA8)") (class "Default")
      (node (ref "U1") (pin "AA8") (pinfunction "IO_L11P_5_AA8") (pintype "bidirectional+no_connect"))
    )
    (net (code "489") (name "unconnected-(U1B-IO_L12N_5-PadAD8)") (class "Default")
      (node (ref "U1") (pin "AD8") (pinfunction "IO_L12N_5_AD8") (pintype "bidirectional+no_connect"))
    )
    (net (code "490") (name "unconnected-(U1B-IO_L12P_5-PadAC8)") (class "Default")
      (node (ref "U1") (pin "AC8") (pinfunction "IO_L12P_5_AC8") (pintype "bidirectional+no_connect"))
    )
    (net (code "491") (name "unconnected-(U1B-IO_L18N_5-PadAE9)") (class "Default")
      (node (ref "U1") (pin "AE9") (pinfunction "IO_L18N_5_AE9") (pintype "bidirectional+no_connect"))
    )
    (net (code "492") (name "unconnected-(U1B-IO_L18P_5-PadAD9)") (class "Default")
      (node (ref "U1") (pin "AD9") (pinfunction "IO_L18P_5_AD9") (pintype "bidirectional+no_connect"))
    )
    (net (code "493") (name "unconnected-(U1B-IO_L23N_5-PadAF10)") (class "Default")
      (node (ref "U1") (pin "AF10") (pinfunction "IO_L23N_5_AF10") (pintype "bidirectional+no_connect"))
    )
    (net (code "494") (name "unconnected-(U1B-IO_L23P_5-PadAE10)") (class "Default")
      (node (ref "U1") (pin "AE10") (pinfunction "IO_L23P_5_AE10") (pintype "bidirectional+no_connect"))
    )
    (net (code "495") (name "unconnected-(U1B-IO_L26N_5-PadAF11)") (class "Default")
      (node (ref "U1") (pin "AF11") (pinfunction "IO_L26N_5_AF11") (pintype "bidirectional+no_connect"))
    )
    (net (code "496") (name "unconnected-(U1B-IO_L26P_5-PadAE11)") (class "Default")
      (node (ref "U1") (pin "AE11") (pinfunction "IO_L26P_5_AE11") (pintype "bidirectional+no_connect"))
    )
    (net (code "497") (name "unconnected-(U1B-IO_L32N_1{slash}GCLK5-PadB14)") (class "Default")
      (node (ref "U1") (pin "B14") (pinfunction "IO_L32N_1/GCLK5_B14") (pintype "bidirectional+no_connect"))
    )
  )
)
